# busmon.net
KiCad netlist of a schematic drawn in EAGLE
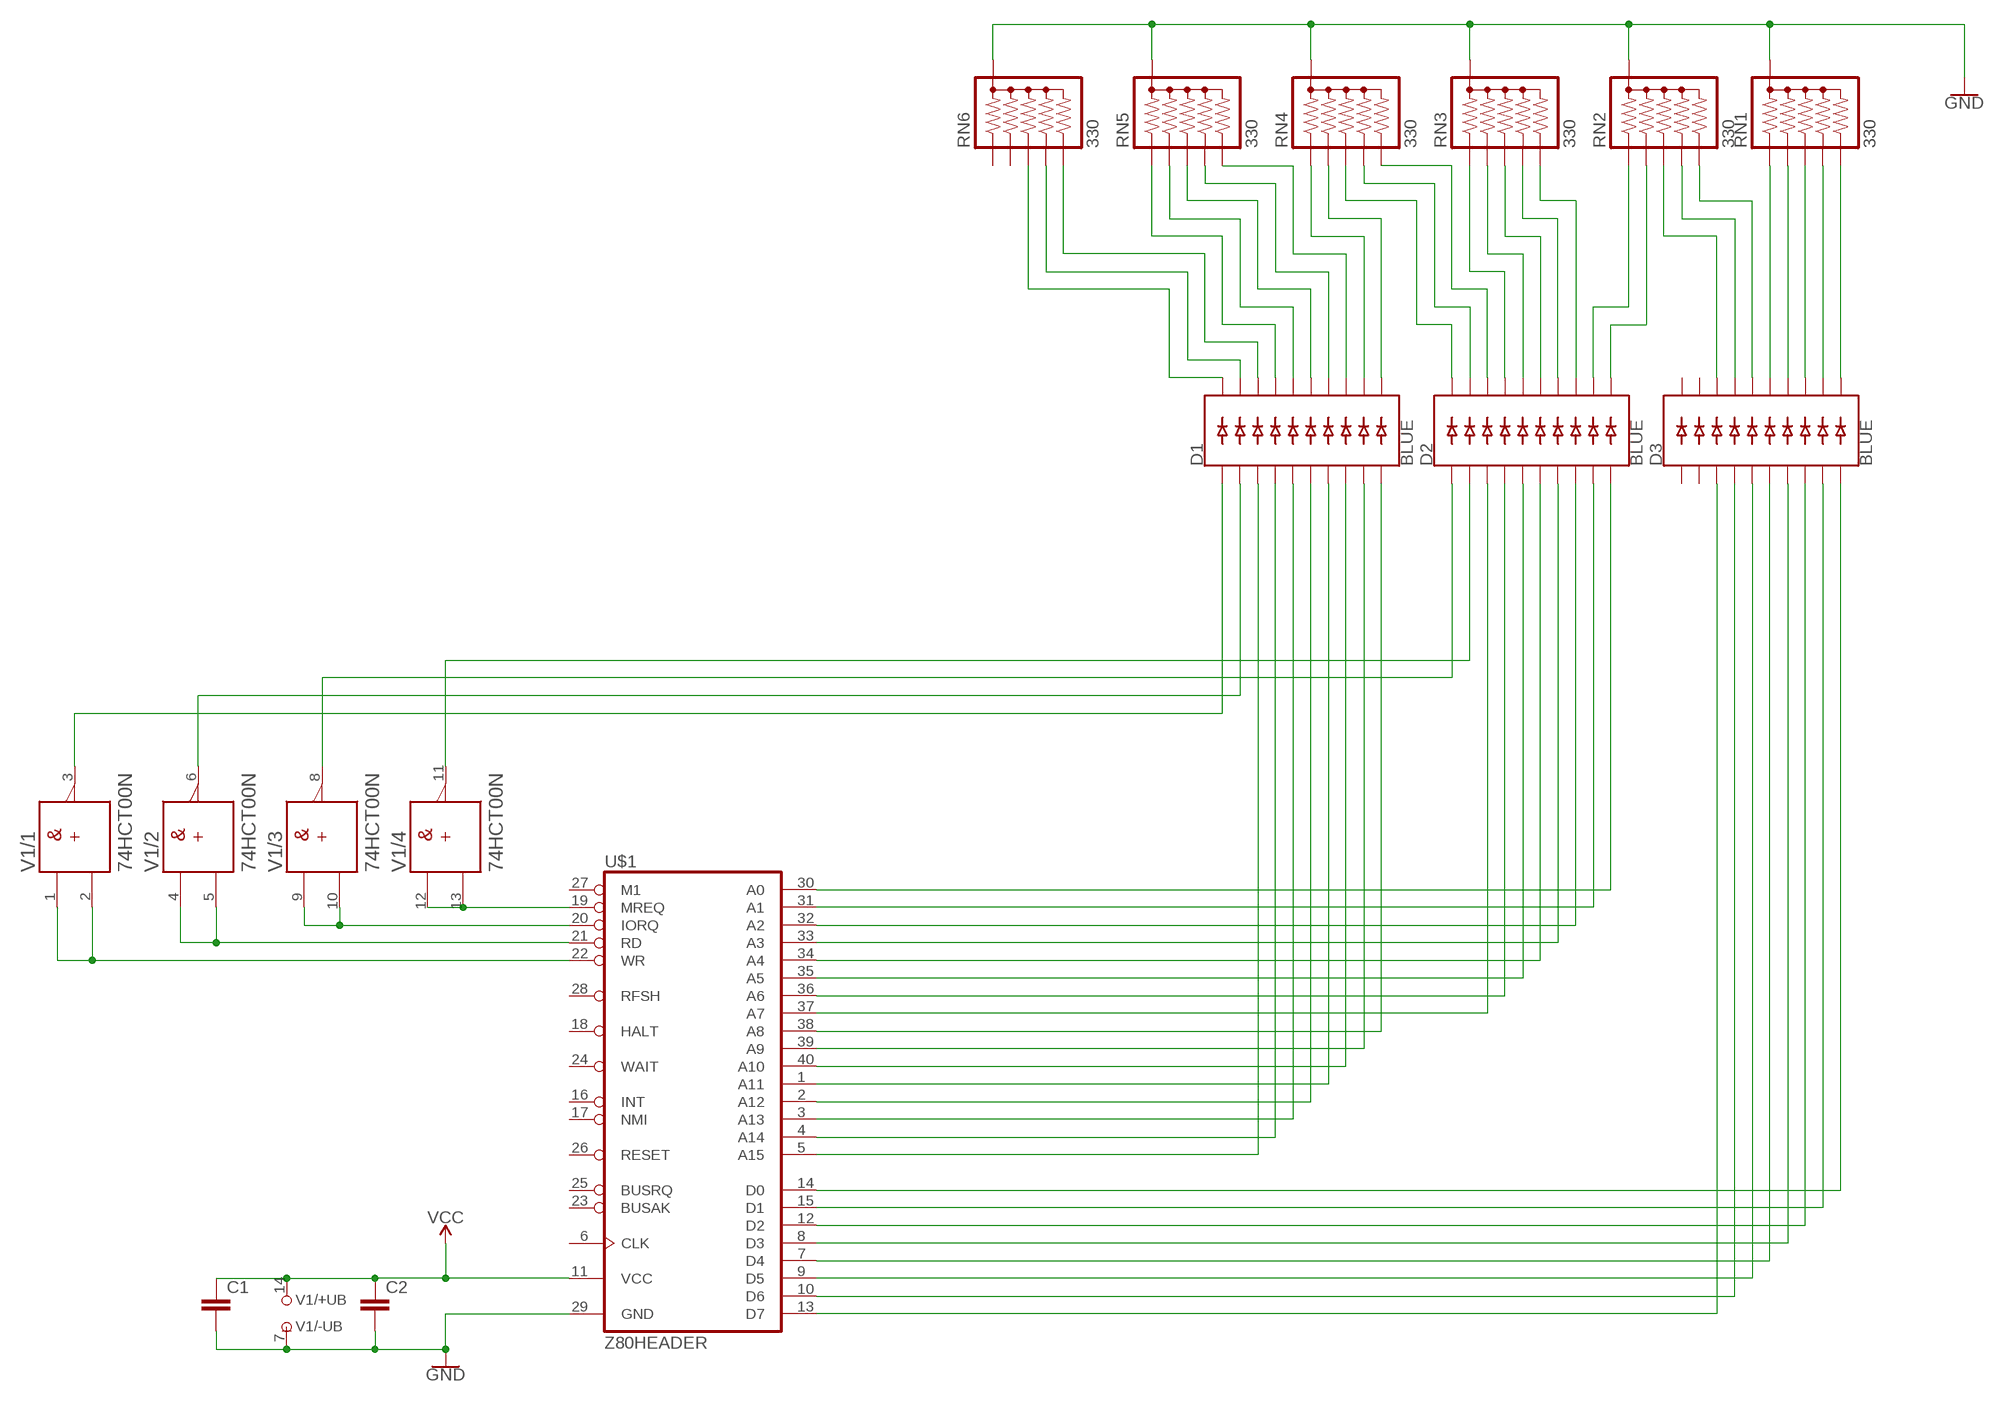
[diagram p0: schematic, sheet 1]

(export (version "E")
  (design (tool "Eeschema 10.0.6"))
  (components
    (comp (ref "C1")
      (value "C2,5-3")
      (footprint "eagle-import:C2.5-3")
      (libsource (lib "eagle-import") (part "C2,5-3"))
    )
    (comp (ref "C2")
      (value "C2,5-3")
      (footprint "eagle-import:C2.5-3")
      (libsource (lib "eagle-import") (part "C2,5-3"))
    )
    (comp (ref "D1")
      (value "BLUE")
      (footprint "eagle-import:LED_BARGRAPH_10")
      (libsource (lib "eagle-import") (part "LED_BARGRAPH_10BLUE"))
    )
    (comp (ref "D2")
      (value "BLUE")
      (footprint "eagle-import:LED_BARGRAPH_10")
      (libsource (lib "eagle-import") (part "LED_BARGRAPH_10BLUE"))
    )
    (comp (ref "D3")
      (value "BLUE")
      (footprint "eagle-import:LED_BARGRAPH_10")
      (libsource (lib "eagle-import") (part "LED_BARGRAPH_10BLUE"))
    )
    (comp (ref "RN1")
      (value "330")
      (footprint "eagle-import:RPACK-SIP-PTH-5")
      (libsource (lib "eagle-import") (part "330_BUSSED_5"))
    )
    (comp (ref "RN2")
      (value "330")
      (footprint "eagle-import:RPACK-SIP-PTH-5")
      (libsource (lib "eagle-import") (part "330_BUSSED_5"))
    )
    (comp (ref "RN3")
      (value "330")
      (footprint "eagle-import:RPACK-SIP-PTH-5")
      (libsource (lib "eagle-import") (part "330_BUSSED_5"))
    )
    (comp (ref "RN4")
      (value "330")
      (footprint "eagle-import:RPACK-SIP-PTH-5")
      (libsource (lib "eagle-import") (part "330_BUSSED_5"))
    )
    (comp (ref "RN5")
      (value "330")
      (footprint "eagle-import:RPACK-SIP-PTH-5")
      (libsource (lib "eagle-import") (part "330_BUSSED_5"))
    )
    (comp (ref "RN6")
      (value "330")
      (footprint "eagle-import:RPACK-SIP-PTH-5")
      (libsource (lib "eagle-import") (part "330_BUSSED_5"))
    )
    (comp (ref "U$1")
      (value "Z80HEADER")
      (footprint "eagle-import:2X20")
      (libsource (lib "eagle-import") (part "Z80HEADER"))
    )
    (comp (ref "V1")
      (value "74HCT00N")
      (footprint "eagle-import:DIL14")
      (libsource (lib "eagle-import") (part "7400NHCT"))
    )
  )
  (nets
    (net (code "1") (name "GND") (class "Default")
      (node (ref "C1") (pin "2") (pinfunction "2_2") (pintype "passive"))
      (node (ref "C2") (pin "2") (pinfunction "2_2") (pintype "passive"))
      (node (ref "RN1") (pin "P$1") (pinfunction "1_P$1") (pintype "passive"))
      (node (ref "RN2") (pin "P$1") (pinfunction "1_P$1") (pintype "passive"))
      (node (ref "RN3") (pin "P$1") (pinfunction "1_P$1") (pintype "passive"))
      (node (ref "RN4") (pin "P$1") (pinfunction "1_P$1") (pintype "passive"))
      (node (ref "RN5") (pin "P$1") (pinfunction "1_P$1") (pintype "passive"))
      (node (ref "RN6") (pin "P$1") (pinfunction "1_P$1") (pintype "passive"))
      (node (ref "U$1") (pin "29") (pinfunction "GND_29") (pintype "power_in"))
      (node (ref "V1") (pin "7") (pinfunction "-UB_7") (pintype "power_in"))
    )
    (net (code "2") (name "Net-(D1-A)") (class "Default")
      (node (ref "D1") (pin "1") (pinfunction "A_1") (pintype "passive"))
      (node (ref "V1") (pin "3") (pinfunction "Y_3") (pintype "output"))
    )
    (net (code "3") (name "Net-(D1-A1)") (class "Default")
      (node (ref "D1") (pin "2") (pinfunction "A1_2") (pintype "passive"))
      (node (ref "V1") (pin "6") (pinfunction "Y_6") (pintype "output"))
    )
    (net (code "4") (name "Net-(D1-A2)") (class "Default")
      (node (ref "D1") (pin "3") (pinfunction "A2_3") (pintype "passive"))
      (node (ref "U$1") (pin "5") (pinfunction "A15_5") (pintype "output"))
    )
    (net (code "5") (name "Net-(D1-A3)") (class "Default")
      (node (ref "D1") (pin "4") (pinfunction "A3_4") (pintype "passive"))
      (node (ref "U$1") (pin "4") (pinfunction "A14_4") (pintype "output"))
    )
    (net (code "6") (name "Net-(D1-A4)") (class "Default")
      (node (ref "D1") (pin "5") (pinfunction "A4_5") (pintype "passive"))
      (node (ref "U$1") (pin "3") (pinfunction "A13_3") (pintype "output"))
    )
    (net (code "7") (name "Net-(D1-A5)") (class "Default")
      (node (ref "D1") (pin "6") (pinfunction "A5_6") (pintype "passive"))
      (node (ref "U$1") (pin "2") (pinfunction "A12_2") (pintype "output"))
    )
    (net (code "8") (name "Net-(D1-A6)") (class "Default")
      (node (ref "D1") (pin "7") (pinfunction "A6_7") (pintype "passive"))
      (node (ref "U$1") (pin "1") (pinfunction "A11_1") (pintype "output"))
    )
    (net (code "9") (name "Net-(D1-A7)") (class "Default")
      (node (ref "D1") (pin "8") (pinfunction "A7_8") (pintype "passive"))
      (node (ref "U$1") (pin "40") (pinfunction "A10_40") (pintype "output"))
    )
    (net (code "10") (name "Net-(D1-A8)") (class "Default")
      (node (ref "D1") (pin "9") (pinfunction "A8_9") (pintype "passive"))
      (node (ref "U$1") (pin "39") (pinfunction "A9_39") (pintype "output"))
    )
    (net (code "11") (name "Net-(D1-A9)") (class "Default")
      (node (ref "D1") (pin "10") (pinfunction "A9_10") (pintype "passive"))
      (node (ref "U$1") (pin "38") (pinfunction "A8_38") (pintype "output"))
    )
    (net (code "12") (name "Net-(D1-C)") (class "Default")
      (node (ref "D1") (pin "20") (pinfunction "C_20") (pintype "passive"))
      (node (ref "RN6") (pin "P$4") (pinfunction "4_P$4") (pintype "passive"))
    )
    (net (code "13") (name "Net-(D1-C1)") (class "Default")
      (node (ref "D1") (pin "19") (pinfunction "C1_19") (pintype "passive"))
      (node (ref "RN6") (pin "P$5") (pinfunction "5_P$5") (pintype "passive"))
    )
    (net (code "14") (name "Net-(D1-C2)") (class "Default")
      (node (ref "D1") (pin "18") (pinfunction "C2_18") (pintype "passive"))
      (node (ref "RN6") (pin "P$6") (pinfunction "6_P$6") (pintype "passive"))
    )
    (net (code "15") (name "Net-(D1-C3)") (class "Default")
      (node (ref "D1") (pin "17") (pinfunction "C3_17") (pintype "passive"))
      (node (ref "RN5") (pin "P$2") (pinfunction "2_P$2") (pintype "passive"))
    )
    (net (code "16") (name "Net-(D1-C4)") (class "Default")
      (node (ref "D1") (pin "16") (pinfunction "C4_16") (pintype "passive"))
      (node (ref "RN5") (pin "P$3") (pinfunction "3_P$3") (pintype "passive"))
    )
    (net (code "17") (name "Net-(D1-C5)") (class "Default")
      (node (ref "D1") (pin "15") (pinfunction "C5_15") (pintype "passive"))
      (node (ref "RN5") (pin "P$4") (pinfunction "4_P$4") (pintype "passive"))
    )
    (net (code "18") (name "Net-(D1-C6)") (class "Default")
      (node (ref "D1") (pin "14") (pinfunction "C6_14") (pintype "passive"))
      (node (ref "RN5") (pin "P$5") (pinfunction "5_P$5") (pintype "passive"))
    )
    (net (code "19") (name "Net-(D1-C7)") (class "Default")
      (node (ref "D1") (pin "13") (pinfunction "C7_13") (pintype "passive"))
      (node (ref "RN5") (pin "P$6") (pinfunction "6_P$6") (pintype "passive"))
    )
    (net (code "20") (name "Net-(D1-C8)") (class "Default")
      (node (ref "D1") (pin "12") (pinfunction "C8_12") (pintype "passive"))
      (node (ref "RN4") (pin "P$2") (pinfunction "2_P$2") (pintype "passive"))
    )
    (net (code "21") (name "Net-(D1-C9)") (class "Default")
      (node (ref "D1") (pin "11") (pinfunction "C9_11") (pintype "passive"))
      (node (ref "RN4") (pin "P$3") (pinfunction "3_P$3") (pintype "passive"))
    )
    (net (code "22") (name "Net-(D2-A)") (class "Default")
      (node (ref "D2") (pin "1") (pinfunction "A_1") (pintype "passive"))
      (node (ref "V1") (pin "8") (pinfunction "Y_8") (pintype "output"))
    )
    (net (code "23") (name "Net-(D2-A1)") (class "Default")
      (node (ref "D2") (pin "2") (pinfunction "A1_2") (pintype "passive"))
      (node (ref "V1") (pin "11") (pinfunction "Y_11") (pintype "output"))
    )
    (net (code "24") (name "Net-(D2-A2)") (class "Default")
      (node (ref "D2") (pin "3") (pinfunction "A2_3") (pintype "passive"))
      (node (ref "U$1") (pin "37") (pinfunction "A7_37") (pintype "output"))
    )
    (net (code "25") (name "Net-(D2-A3)") (class "Default")
      (node (ref "D2") (pin "4") (pinfunction "A3_4") (pintype "passive"))
      (node (ref "U$1") (pin "36") (pinfunction "A6_36") (pintype "output"))
    )
    (net (code "26") (name "Net-(D2-A4)") (class "Default")
      (node (ref "D2") (pin "5") (pinfunction "A4_5") (pintype "passive"))
      (node (ref "U$1") (pin "35") (pinfunction "A5_35") (pintype "output"))
    )
    (net (code "27") (name "Net-(D2-A5)") (class "Default")
      (node (ref "D2") (pin "6") (pinfunction "A5_6") (pintype "passive"))
      (node (ref "U$1") (pin "34") (pinfunction "A4_34") (pintype "output"))
    )
    (net (code "28") (name "Net-(D2-A6)") (class "Default")
      (node (ref "D2") (pin "7") (pinfunction "A6_7") (pintype "passive"))
      (node (ref "U$1") (pin "33") (pinfunction "A3_33") (pintype "output"))
    )
    (net (code "29") (name "Net-(D2-A7)") (class "Default")
      (node (ref "D2") (pin "8") (pinfunction "A7_8") (pintype "passive"))
      (node (ref "U$1") (pin "32") (pinfunction "A2_32") (pintype "output"))
    )
    (net (code "30") (name "Net-(D2-A8)") (class "Default")
      (node (ref "D2") (pin "9") (pinfunction "A8_9") (pintype "passive"))
      (node (ref "U$1") (pin "31") (pinfunction "A1_31") (pintype "output"))
    )
    (net (code "31") (name "Net-(D2-A9)") (class "Default")
      (node (ref "D2") (pin "10") (pinfunction "A9_10") (pintype "passive"))
      (node (ref "U$1") (pin "30") (pinfunction "A0_30") (pintype "output"))
    )
    (net (code "32") (name "Net-(D2-C)") (class "Default")
      (node (ref "D2") (pin "20") (pinfunction "C_20") (pintype "passive"))
      (node (ref "RN4") (pin "P$4") (pinfunction "4_P$4") (pintype "passive"))
    )
    (net (code "33") (name "Net-(D2-C1)") (class "Default")
      (node (ref "D2") (pin "19") (pinfunction "C1_19") (pintype "passive"))
      (node (ref "RN4") (pin "P$5") (pinfunction "5_P$5") (pintype "passive"))
    )
    (net (code "34") (name "Net-(D2-C2)") (class "Default")
      (node (ref "D2") (pin "18") (pinfunction "C2_18") (pintype "passive"))
      (node (ref "RN4") (pin "P$6") (pinfunction "6_P$6") (pintype "passive"))
    )
    (net (code "35") (name "Net-(D2-C3)") (class "Default")
      (node (ref "D2") (pin "17") (pinfunction "C3_17") (pintype "passive"))
      (node (ref "RN3") (pin "P$2") (pinfunction "2_P$2") (pintype "passive"))
    )
    (net (code "36") (name "Net-(D2-C4)") (class "Default")
      (node (ref "D2") (pin "16") (pinfunction "C4_16") (pintype "passive"))
      (node (ref "RN3") (pin "P$3") (pinfunction "3_P$3") (pintype "passive"))
    )
    (net (code "37") (name "Net-(D2-C5)") (class "Default")
      (node (ref "D2") (pin "15") (pinfunction "C5_15") (pintype "passive"))
      (node (ref "RN3") (pin "P$4") (pinfunction "4_P$4") (pintype "passive"))
    )
    (net (code "38") (name "Net-(D2-C6)") (class "Default")
      (node (ref "D2") (pin "14") (pinfunction "C6_14") (pintype "passive"))
      (node (ref "RN3") (pin "P$5") (pinfunction "5_P$5") (pintype "passive"))
    )
    (net (code "39") (name "Net-(D2-C7)") (class "Default")
      (node (ref "D2") (pin "13") (pinfunction "C7_13") (pintype "passive"))
      (node (ref "RN3") (pin "P$6") (pinfunction "6_P$6") (pintype "passive"))
    )
    (net (code "40") (name "Net-(D2-C8)") (class "Default")
      (node (ref "D2") (pin "12") (pinfunction "C8_12") (pintype "passive"))
      (node (ref "RN2") (pin "P$2") (pinfunction "2_P$2") (pintype "passive"))
    )
    (net (code "41") (name "Net-(D2-C9)") (class "Default")
      (node (ref "D2") (pin "11") (pinfunction "C9_11") (pintype "passive"))
      (node (ref "RN2") (pin "P$3") (pinfunction "3_P$3") (pintype "passive"))
    )
    (net (code "42") (name "Net-(D3-A2)") (class "Default")
      (node (ref "D3") (pin "3") (pinfunction "A2_3") (pintype "passive"))
      (node (ref "U$1") (pin "13") (pinfunction "D7_13") (pintype "bidirectional"))
    )
    (net (code "43") (name "Net-(D3-A3)") (class "Default")
      (node (ref "D3") (pin "4") (pinfunction "A3_4") (pintype "passive"))
      (node (ref "U$1") (pin "10") (pinfunction "D6_10") (pintype "bidirectional"))
    )
    (net (code "44") (name "Net-(D3-A4)") (class "Default")
      (node (ref "D3") (pin "5") (pinfunction "A4_5") (pintype "passive"))
      (node (ref "U$1") (pin "9") (pinfunction "D5_9") (pintype "bidirectional"))
    )
    (net (code "45") (name "Net-(D3-A5)") (class "Default")
      (node (ref "D3") (pin "6") (pinfunction "A5_6") (pintype "passive"))
      (node (ref "U$1") (pin "7") (pinfunction "D4_7") (pintype "bidirectional"))
    )
    (net (code "46") (name "Net-(D3-A6)") (class "Default")
      (node (ref "D3") (pin "7") (pinfunction "A6_7") (pintype "passive"))
      (node (ref "U$1") (pin "8") (pinfunction "D3_8") (pintype "bidirectional"))
    )
    (net (code "47") (name "Net-(D3-A7)") (class "Default")
      (node (ref "D3") (pin "8") (pinfunction "A7_8") (pintype "passive"))
      (node (ref "U$1") (pin "12") (pinfunction "D2_12") (pintype "bidirectional"))
    )
    (net (code "48") (name "Net-(D3-A8)") (class "Default")
      (node (ref "D3") (pin "9") (pinfunction "A8_9") (pintype "passive"))
      (node (ref "U$1") (pin "15") (pinfunction "D1_15") (pintype "bidirectional"))
    )
    (net (code "49") (name "Net-(D3-A9)") (class "Default")
      (node (ref "D3") (pin "10") (pinfunction "A9_10") (pintype "passive"))
      (node (ref "U$1") (pin "14") (pinfunction "D0_14") (pintype "bidirectional"))
    )
    (net (code "50") (name "Net-(D3-C2)") (class "Default")
      (node (ref "D3") (pin "18") (pinfunction "C2_18") (pintype "passive"))
      (node (ref "RN2") (pin "P$4") (pinfunction "4_P$4") (pintype "passive"))
    )
    (net (code "51") (name "Net-(D3-C3)") (class "Default")
      (node (ref "D3") (pin "17") (pinfunction "C3_17") (pintype "passive"))
      (node (ref "RN2") (pin "P$5") (pinfunction "5_P$5") (pintype "passive"))
    )
    (net (code "52") (name "Net-(D3-C4)") (class "Default")
      (node (ref "D3") (pin "16") (pinfunction "C4_16") (pintype "passive"))
      (node (ref "RN2") (pin "P$6") (pinfunction "6_P$6") (pintype "passive"))
    )
    (net (code "53") (name "Net-(D3-C5)") (class "Default")
      (node (ref "D3") (pin "15") (pinfunction "C5_15") (pintype "passive"))
      (node (ref "RN1") (pin "P$2") (pinfunction "2_P$2") (pintype "passive"))
    )
    (net (code "54") (name "Net-(D3-C6)") (class "Default")
      (node (ref "D3") (pin "14") (pinfunction "C6_14") (pintype "passive"))
      (node (ref "RN1") (pin "P$3") (pinfunction "3_P$3") (pintype "passive"))
    )
    (net (code "55") (name "Net-(D3-C7)") (class "Default")
      (node (ref "D3") (pin "13") (pinfunction "C7_13") (pintype "passive"))
      (node (ref "RN1") (pin "P$4") (pinfunction "4_P$4") (pintype "passive"))
    )
    (net (code "56") (name "Net-(D3-C8)") (class "Default")
      (node (ref "D3") (pin "12") (pinfunction "C8_12") (pintype "passive"))
      (node (ref "RN1") (pin "P$5") (pinfunction "5_P$5") (pintype "passive"))
    )
    (net (code "57") (name "Net-(D3-C9)") (class "Default")
      (node (ref "D3") (pin "11") (pinfunction "C9_11") (pintype "passive"))
      (node (ref "RN1") (pin "P$6") (pinfunction "6_P$6") (pintype "passive"))
    )
    (net (code "58") (name "Net-(U$1-IORQ)") (class "Default")
      (node (ref "U$1") (pin "20") (pinfunction "IORQ_20") (pintype "output"))
      (node (ref "V1") (pin "10") (pinfunction "B_10") (pintype "input"))
      (node (ref "V1") (pin "9") (pinfunction "A_9") (pintype "input"))
    )
    (net (code "59") (name "Net-(U$1-MREQ)") (class "Default")
      (node (ref "U$1") (pin "19") (pinfunction "MREQ_19") (pintype "output"))
      (node (ref "V1") (pin "12") (pinfunction "A_12") (pintype "input"))
      (node (ref "V1") (pin "13") (pinfunction "B_13") (pintype "input"))
    )
    (net (code "60") (name "Net-(U$1-RD)") (class "Default")
      (node (ref "U$1") (pin "21") (pinfunction "RD_21") (pintype "output"))
      (node (ref "V1") (pin "4") (pinfunction "A_4") (pintype "input"))
      (node (ref "V1") (pin "5") (pinfunction "B_5") (pintype "input"))
    )
    (net (code "61") (name "Net-(U$1-WR)") (class "Default")
      (node (ref "U$1") (pin "22") (pinfunction "WR_22") (pintype "output"))
      (node (ref "V1") (pin "1") (pinfunction "A_1") (pintype "input"))
      (node (ref "V1") (pin "2") (pinfunction "B_2") (pintype "input"))
    )
    (net (code "62") (name "VCC") (class "Default")
      (node (ref "C1") (pin "1") (pinfunction "1_1") (pintype "passive"))
      (node (ref "C2") (pin "1") (pinfunction "1_1") (pintype "passive"))
      (node (ref "U$1") (pin "11") (pinfunction "VCC_11") (pintype "power_in"))
      (node (ref "V1") (pin "14") (pinfunction "+UB_14") (pintype "power_in"))
    )
    (net (code "63") (name "unconnected-(D3-A-Pad1)") (class "Default")
      (node (ref "D3") (pin "1") (pinfunction "A_1") (pintype "passive"))
    )
    (net (code "64") (name "unconnected-(D3-A1-Pad2)") (class "Default")
      (node (ref "D3") (pin "2") (pinfunction "A1_2") (pintype "passive"))
    )
    (net (code "65") (name "unconnected-(D3-C-Pad20)") (class "Default")
      (node (ref "D3") (pin "20") (pinfunction "C_20") (pintype "passive"))
    )
    (net (code "66") (name "unconnected-(D3-C1-Pad19)") (class "Default")
      (node (ref "D3") (pin "19") (pinfunction "C1_19") (pintype "passive"))
    )
    (net (code "67") (name "unconnected-(RN6-2-PadP$2)") (class "Default")
      (node (ref "RN6") (pin "P$2") (pinfunction "2_P$2") (pintype "passive"))
    )
    (net (code "68") (name "unconnected-(RN6-3-PadP$3)") (class "Default")
      (node (ref "RN6") (pin "P$3") (pinfunction "3_P$3") (pintype "passive"))
    )
    (net (code "69") (name "unconnected-(U$1-BUSAK-Pad23)") (class "Default")
      (node (ref "U$1") (pin "23") (pinfunction "BUSAK_23") (pintype "output"))
    )
    (net (code "70") (name "unconnected-(U$1-BUSRQ-Pad25)") (class "Default")
      (node (ref "U$1") (pin "25") (pinfunction "BUSRQ_25") (pintype "input"))
    )
    (net (code "71") (name "unconnected-(U$1-CLK-Pad6)") (class "Default")
      (node (ref "U$1") (pin "6") (pinfunction "CLK_6") (pintype "input"))
    )
    (net (code "72") (name "unconnected-(U$1-HALT-Pad18)") (class "Default")
      (node (ref "U$1") (pin "18") (pinfunction "HALT_18") (pintype "output"))
    )
    (net (code "73") (name "unconnected-(U$1-INT-Pad16)") (class "Default")
      (node (ref "U$1") (pin "16") (pinfunction "INT_16") (pintype "input"))
    )
    (net (code "74") (name "unconnected-(U$1-M1-Pad27)") (class "Default")
      (node (ref "U$1") (pin "27") (pinfunction "M1_27") (pintype "output"))
    )
    (net (code "75") (name "unconnected-(U$1-NMI-Pad17)") (class "Default")
      (node (ref "U$1") (pin "17") (pinfunction "NMI_17") (pintype "input"))
    )
    (net (code "76") (name "unconnected-(U$1-RESET-Pad26)") (class "Default")
      (node (ref "U$1") (pin "26") (pinfunction "RESET_26") (pintype "input"))
    )
    (net (code "77") (name "unconnected-(U$1-RFSH-Pad28)") (class "Default")
      (node (ref "U$1") (pin "28") (pinfunction "RFSH_28") (pintype "output"))
    )
    (net (code "78") (name "unconnected-(U$1-WAIT-Pad24)") (class "Default")
      (node (ref "U$1") (pin "24") (pinfunction "WAIT_24") (pintype "input"))
    )
  )
)
